# tema.net
KiCad netlist of a schematic drawn in EAGLE
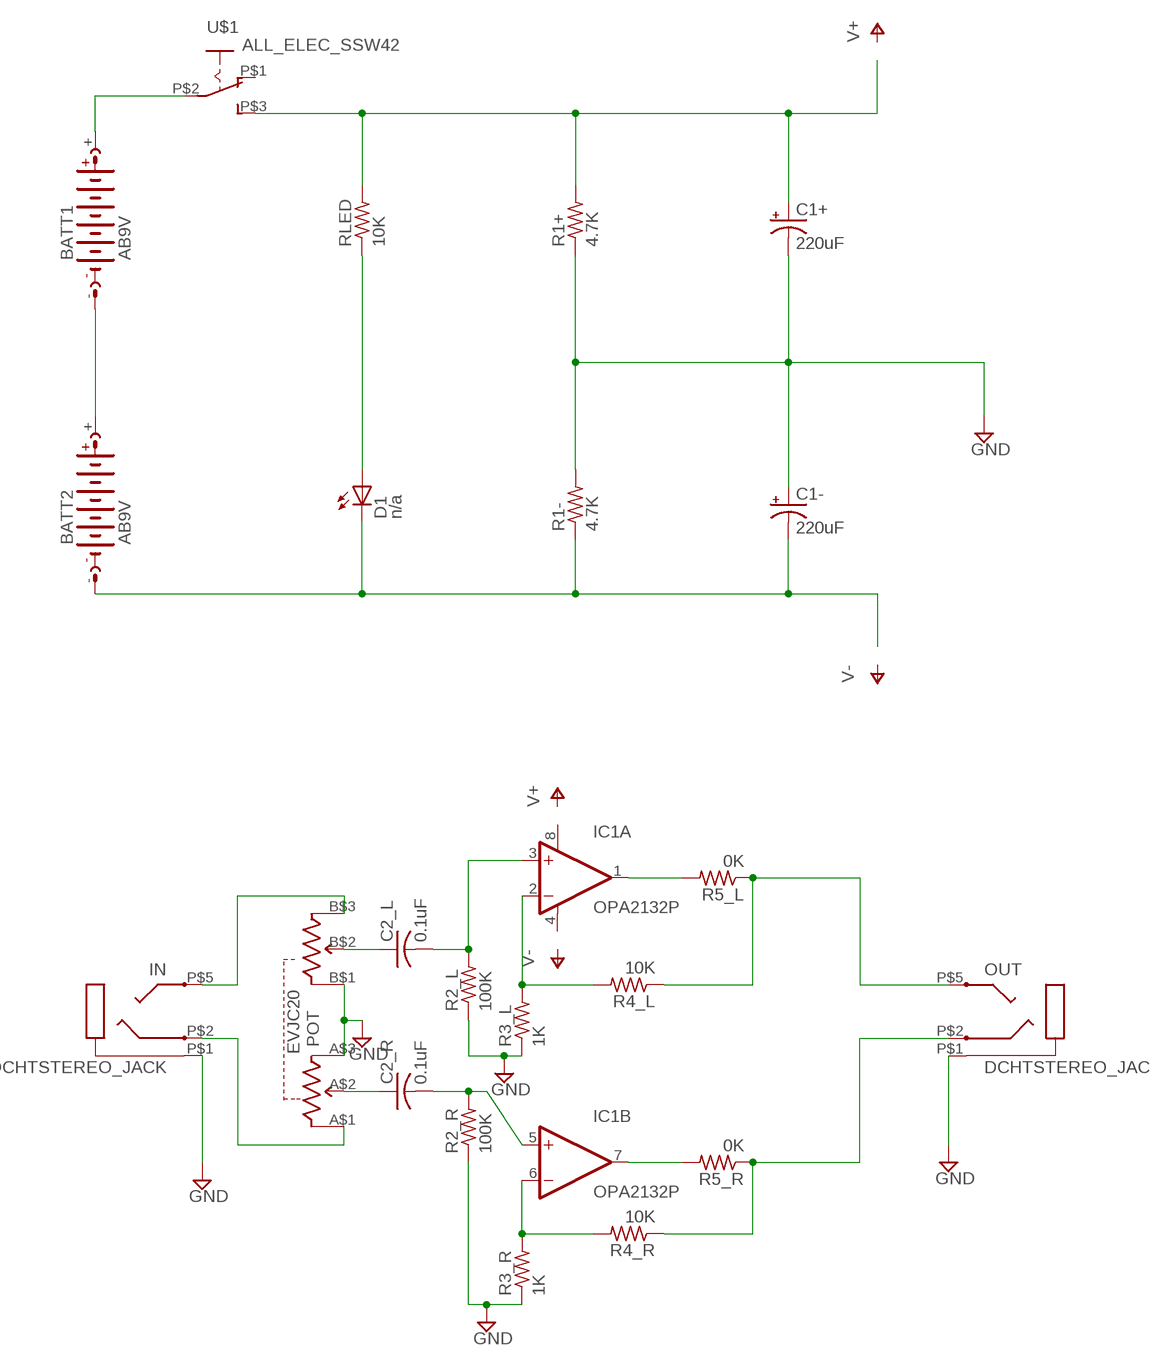
[diagram p0: schematic, sheet 1]

(export (version "E")
  (design (tool "Eeschema 10.0.6"))
  (components
    (comp (ref "BATT1")
      (value "AB9V")
      (footprint "eagle-import:AB9V")
      (libsource (lib "eagle-import") (part "AB9V"))
    )
    (comp (ref "BATT2")
      (value "AB9V")
      (footprint "eagle-import:AB9V")
      (libsource (lib "eagle-import") (part "AB9V"))
    )
    (comp (ref "C1+")
      (value "220uF")
      (footprint "eagle-import:E3,5-8")
      (libsource (lib "eagle-import") (part "CPOL-USE3.5-8"))
    )
    (comp (ref "C1-")
      (value "220uF")
      (footprint "eagle-import:E3,5-8")
      (libsource (lib "eagle-import") (part "CPOL-USE3.5-8"))
    )
    (comp (ref "C2_L")
      (value "0.1uF")
      (footprint "eagle-import:C075-052X106")
      (libsource (lib "eagle-import") (part "C-US075-052X106"))
    )
    (comp (ref "C2_R")
      (value "0.1uF")
      (footprint "eagle-import:C075-052X106")
      (libsource (lib "eagle-import") (part "C-US075-052X106"))
    )
    (comp (ref "D1")
      (value "n/a")
      (footprint "eagle-import:LED5MM")
      (libsource (lib "eagle-import") (part "LED5MM"))
    )
    (comp (ref "IC1")
      (value "OPA2132P")
      (footprint "eagle-import:DIL08")
      (libsource (lib "eagle-import") (part "OPA2132P"))
    )
    (comp (ref "IN")
      (value "DCHTSTEREO_JACK")
      (footprint "eagle-import:DCHTSTJACK")
      (libsource (lib "eagle-import") (part "DCHTSTEREO_JACK"))
    )
    (comp (ref "OUT")
      (value "DCHTSTEREO_JACK")
      (footprint "eagle-import:DCHTSTJACK")
      (libsource (lib "eagle-import") (part "DCHTSTEREO_JACK"))
    )
    (comp (ref "POT")
      (value "EVJC20")
      (footprint "eagle-import:PC16D")
      (libsource (lib "eagle-import") (part "EVJC20"))
    )
    (comp (ref "R1+")
      (value "4.7K")
      (footprint "eagle-import:0207_5V")
      (libsource (lib "eagle-import") (part "R-US_0207/5V"))
    )
    (comp (ref "R1-")
      (value "4.7K")
      (footprint "eagle-import:0207_5V")
      (libsource (lib "eagle-import") (part "R-US_0207/5V"))
    )
    (comp (ref "R2_L")
      (value "100K")
      (footprint "eagle-import:0207_7")
      (libsource (lib "eagle-import") (part "R-US_0207/7"))
    )
    (comp (ref "R2_R")
      (value "100K")
      (footprint "eagle-import:0207_7")
      (libsource (lib "eagle-import") (part "R-US_0207/7"))
    )
    (comp (ref "R3_L")
      (value "1K")
      (footprint "eagle-import:0207_7")
      (libsource (lib "eagle-import") (part "R-US_0207/7"))
    )
    (comp (ref "R3_R")
      (value "1K")
      (footprint "eagle-import:0207_7")
      (libsource (lib "eagle-import") (part "R-US_0207/7"))
    )
    (comp (ref "R4_L")
      (value "10K")
      (footprint "eagle-import:0207_7")
      (libsource (lib "eagle-import") (part "R-US_0207/7"))
    )
    (comp (ref "R4_R")
      (value "10K")
      (footprint "eagle-import:0207_7")
      (libsource (lib "eagle-import") (part "R-US_0207/7"))
    )
    (comp (ref "R5_L")
      (value "0K")
      (footprint "eagle-import:0207_7")
      (libsource (lib "eagle-import") (part "R-US_0207/7"))
    )
    (comp (ref "R5_R")
      (value "0K")
      (footprint "eagle-import:0207_7")
      (libsource (lib "eagle-import") (part "R-US_0207/7"))
    )
    (comp (ref "RLED")
      (value "10K")
      (footprint "eagle-import:0207_5V")
      (libsource (lib "eagle-import") (part "R-US_0207/5V"))
    )
    (comp (ref "U$1")
      (value "ALL_ELEC_SSW42")
      (footprint "eagle-import:SSW-42")
      (libsource (lib "eagle-import") (part "ALL_ELEC_SSW42"))
    )
  )
  (nets
    (net (code "1") (name "GND") (class "Default")
      (node (ref "C1+") (pin "-") (pinfunction "-_-") (pintype "passive"))
      (node (ref "C1-") (pin "+") (pinfunction "+_+") (pintype "passive"))
      (node (ref "IN") (pin "P$1") (pinfunction "1_P$1") (pintype "passive"))
      (node (ref "OUT") (pin "P$1") (pinfunction "1_P$1") (pintype "passive"))
      (node (ref "POT") (pin "A$3") (pinfunction "1E_A$3") (pintype "passive"))
      (node (ref "POT") (pin "B$1") (pinfunction "2A_B$1") (pintype "passive"))
      (node (ref "R1+") (pin "1") (pinfunction "1_1") (pintype "passive"))
      (node (ref "R1-") (pin "2") (pinfunction "2_2") (pintype "passive"))
      (node (ref "R2_L") (pin "1") (pinfunction "1_1") (pintype "passive"))
      (node (ref "R2_R") (pin "1") (pinfunction "1_1") (pintype "passive"))
      (node (ref "R3_L") (pin "1") (pinfunction "1_1") (pintype "passive"))
      (node (ref "R3_R") (pin "1") (pinfunction "1_1") (pintype "passive"))
    )
    (net (code "2") (name "Net-(BATT1-Pad-)") (class "Default")
      (node (ref "BATT1") (pin "-") (pinfunction "-_-") (pintype "passive"))
      (node (ref "BATT2") (pin "+") (pinfunction "+_+") (pintype "passive"))
    )
    (net (code "3") (name "Net-(D1-C)") (class "Default")
      (node (ref "BATT2") (pin "-") (pinfunction "-_-") (pintype "passive"))
      (node (ref "C1-") (pin "-") (pinfunction "-_-") (pintype "passive"))
      (node (ref "D1") (pin "K") (pinfunction "C_K") (pintype "passive"))
      (node (ref "R1-") (pin "1") (pinfunction "1_1") (pintype "passive"))
    )
    (net (code "4") (name "Net-(D1-PadA)") (class "Default")
      (node (ref "D1") (pin "A") (pinfunction "A_A") (pintype "passive"))
      (node (ref "RLED") (pin "1") (pinfunction "1_1") (pintype "passive"))
    )
    (net (code "5") (name "Net-(IC1A-+IN)") (class "Default")
      (node (ref "C2_L") (pin "2") (pinfunction "2_2") (pintype "passive"))
      (node (ref "IC1") (pin "3") (pinfunction "+IN_3") (pintype "input"))
      (node (ref "R2_L") (pin "2") (pinfunction "2_2") (pintype "passive"))
    )
    (net (code "6") (name "Net-(IC1A--IN)") (class "Default")
      (node (ref "IC1") (pin "2") (pinfunction "-IN_2") (pintype "input"))
      (node (ref "R3_L") (pin "2") (pinfunction "2_2") (pintype "passive"))
      (node (ref "R4_L") (pin "2") (pinfunction "2_2") (pintype "passive"))
    )
    (net (code "7") (name "Net-(IC1A-OUT)") (class "Default")
      (node (ref "IC1") (pin "1") (pinfunction "OUT_1") (pintype "output"))
      (node (ref "R5_L") (pin "2") (pinfunction "2_2") (pintype "passive"))
    )
    (net (code "8") (name "Net-(IC1B-+IN)") (class "Default")
      (node (ref "C2_R") (pin "2") (pinfunction "2_2") (pintype "passive"))
      (node (ref "IC1") (pin "5") (pinfunction "+IN_5") (pintype "input"))
      (node (ref "R2_R") (pin "2") (pinfunction "2_2") (pintype "passive"))
    )
    (net (code "9") (name "Net-(IC1B--IN)") (class "Default")
      (node (ref "IC1") (pin "6") (pinfunction "-IN_6") (pintype "input"))
      (node (ref "R3_R") (pin "2") (pinfunction "2_2") (pintype "passive"))
      (node (ref "R4_R") (pin "2") (pinfunction "2_2") (pintype "passive"))
    )
    (net (code "10") (name "Net-(IC1B-OUT)") (class "Default")
      (node (ref "IC1") (pin "7") (pinfunction "OUT_7") (pintype "output"))
      (node (ref "R5_R") (pin "2") (pinfunction "2_2") (pintype "passive"))
    )
    (net (code "11") (name "Net-(IN-2)") (class "Default")
      (node (ref "IN") (pin "P$2") (pinfunction "2_P$2") (pintype "passive"))
      (node (ref "POT") (pin "A$1") (pinfunction "1A_A$1") (pintype "passive"))
    )
    (net (code "12") (name "Net-(IN-5)") (class "Default")
      (node (ref "IN") (pin "P$5") (pinfunction "5_P$5") (pintype "passive"))
      (node (ref "POT") (pin "B$3") (pinfunction "2E_B$3") (pintype "passive"))
    )
    (net (code "13") (name "Net-(OUT-2)") (class "Default")
      (node (ref "OUT") (pin "P$2") (pinfunction "2_P$2") (pintype "passive"))
      (node (ref "R4_R") (pin "1") (pinfunction "1_1") (pintype "passive"))
      (node (ref "R5_R") (pin "1") (pinfunction "1_1") (pintype "passive"))
    )
    (net (code "14") (name "Net-(OUT-5)") (class "Default")
      (node (ref "OUT") (pin "P$5") (pinfunction "5_P$5") (pintype "passive"))
      (node (ref "R4_L") (pin "1") (pinfunction "1_1") (pintype "passive"))
      (node (ref "R5_L") (pin "1") (pinfunction "1_1") (pintype "passive"))
    )
    (net (code "15") (name "Net-(POT-1S)") (class "Default")
      (node (ref "C2_R") (pin "1") (pinfunction "1_1") (pintype "passive"))
      (node (ref "POT") (pin "A$2") (pinfunction "1S_A$2") (pintype "passive"))
    )
    (net (code "16") (name "Net-(POT-2S)") (class "Default")
      (node (ref "C2_L") (pin "1") (pinfunction "1_1") (pintype "passive"))
      (node (ref "POT") (pin "B$2") (pinfunction "2S_B$2") (pintype "passive"))
    )
    (net (code "17") (name "Net-(U$1-P)") (class "Default")
      (node (ref "BATT1") (pin "+") (pinfunction "+_+") (pintype "passive"))
      (node (ref "U$1") (pin "P$2") (pinfunction "P_P$2") (pintype "passive"))
    )
    (net (code "18") (name "Net-(U$1-S)") (class "Default")
      (node (ref "C1+") (pin "+") (pinfunction "+_+") (pintype "passive"))
      (node (ref "R1+") (pin "2") (pinfunction "2_2") (pintype "passive"))
      (node (ref "RLED") (pin "2") (pinfunction "2_2") (pintype "passive"))
      (node (ref "U$1") (pin "P$3") (pinfunction "S_P$3") (pintype "passive"))
    )
    (net (code "19") (name "V+") (class "Default")
      (node (ref "IC1") (pin "8") (pinfunction "V+_8") (pintype "power_in"))
    )
    (net (code "20") (name "V-") (class "Default")
      (node (ref "IC1") (pin "4") (pinfunction "V-_4") (pintype "power_in"))
    )
    (net (code "21") (name "unconnected-(U$1-O-PadP$1)") (class "Default")
      (node (ref "U$1") (pin "P$1") (pinfunction "O_P$1") (pintype "passive"))
    )
  )
)
